# CH32V20xG8-R0.net
KiCad netlist of a schematic drawn in Altium Designer
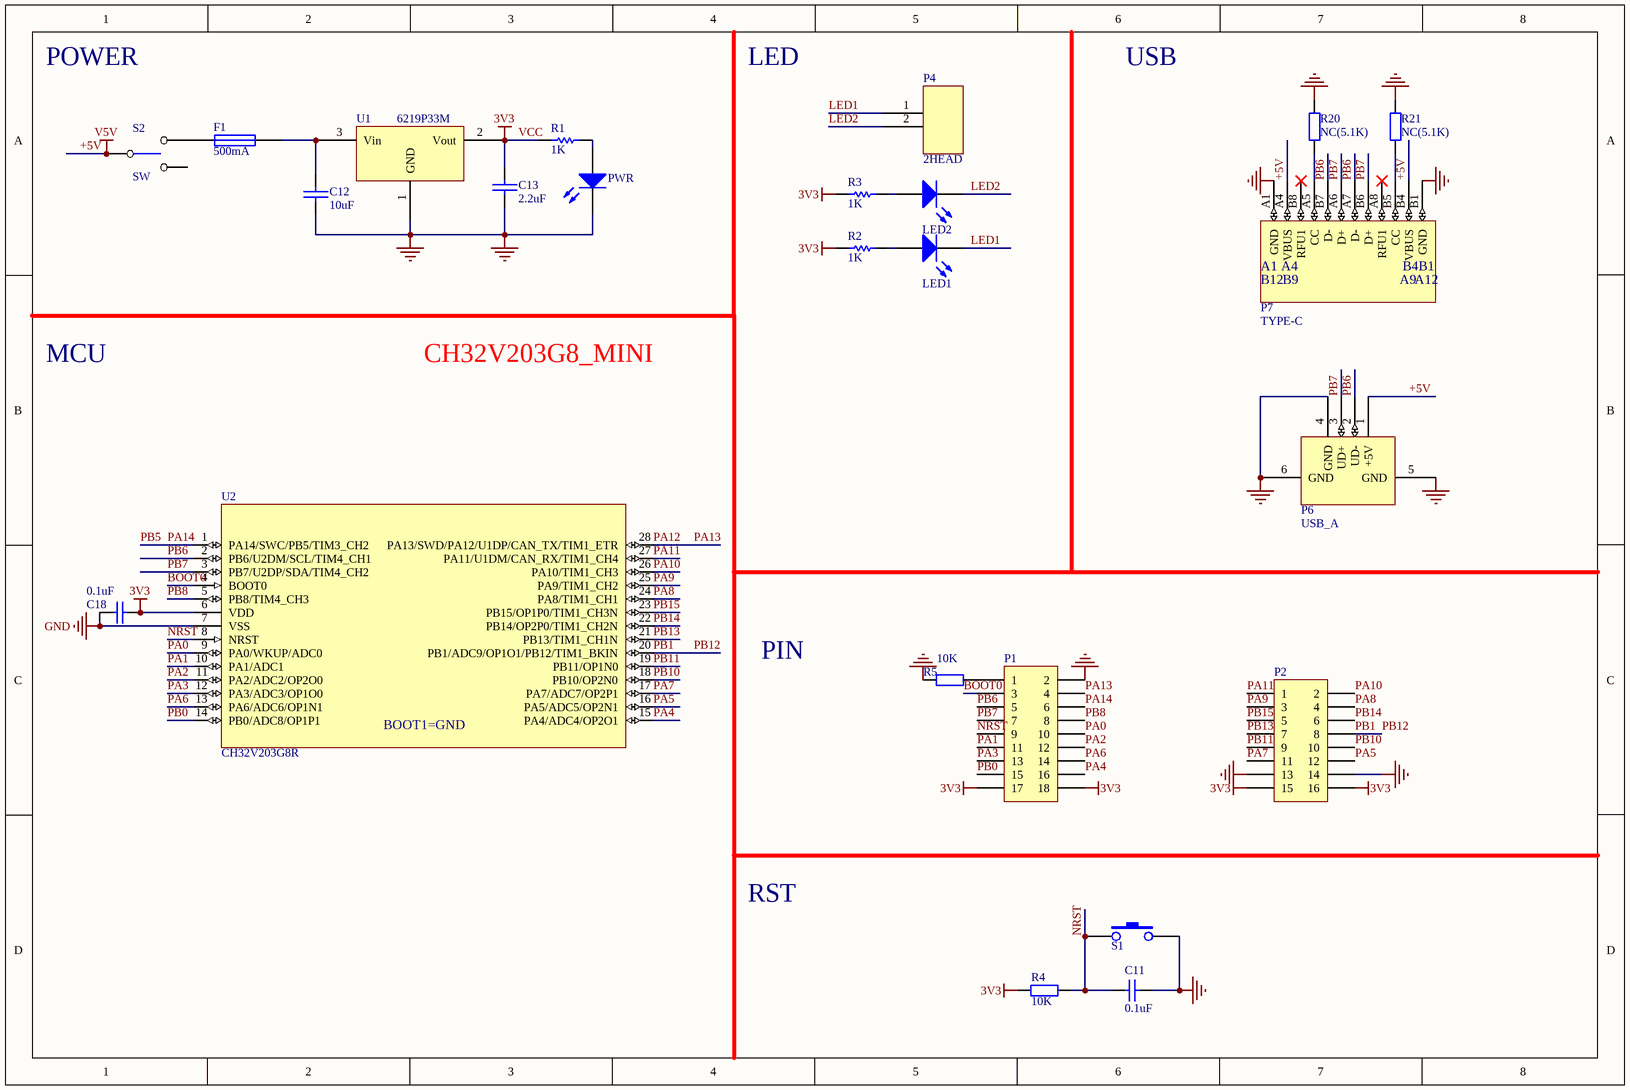
[diagram p0: CH32V20xG8-R0.SchDoc]

(export (version "E")
  (design (tool "Eeschema 10.0.6"))
  (components
    (comp (ref "C11")
      (value "0.1uF")
      (footprint "0603_C")
      (description "Capacitor")
      (fields (field (name "PUBLISHER") "Altium Limited"))
      (libsource (lib "*") (part "Cap"))
    )
    (comp (ref "C12")
      (value "10uF")
      (footprint "3216_C")
      (description "Capacitor")
      (libsource (lib "wch_sch_others") (part "CAP"))
    )
    (comp (ref "C13")
      (value "2.2uF")
      (footprint "0603_C")
      (description "Capacitor")
      (libsource (lib "wch_sch_others") (part "CAP"))
    )
    (comp (ref "C18")
      (value "0.1uF")
      (footprint "0603_C")
      (description "Capacitor")
      (fields (field (name "PUBLISHER") "Altium Limited"))
      (libsource (lib "*") (part "Cap"))
    )
    (comp (ref "F1")
      (value "500mA")
      (footprint "0603")
      (description "Fuse")
      (libsource (lib "*") (part "FUSE1"))
    )
    (comp (ref "LED1")
      (value "LED1   blue")
      (footprint "0603+")
      (description "Typical INFRARED GaAs LED")
      (fields (field (name "PUBLISHER") "Altium Limited"))
      (libsource (lib "*") (part "LED0"))
    )
    (comp (ref "LED2")
      (value "LED2  blue")
      (footprint "0603+")
      (description "Typical INFRARED GaAs LED")
      (fields (field (name "PUBLISHER") "Altium Limited"))
      (libsource (lib "*") (part "LED0"))
    )
    (comp (ref "P1")
      (value "Header 9X2")
      (footprint "IDC18-2.54mm")
      (description "Header, 9-Pin, Dual row")
      (fields (field (name "PUBLISHER") "Altium Limited"))
      (libsource (lib "Miscellaneous Connectors") (part "Header 9X2"))
    )
    (comp (ref "P2")
      (value "Header 8X2")
      (footprint "IDC16-2.54mm")
      (description "Header, 8-Pin, Dual row")
      (fields (field (name "PUBLISHER") "Altium Limited"))
      (libsource (lib "Miscellaneous Connectors") (part "Header 8X2"))
    )
    (comp (ref "P4") (value "2HEAD") (footprint "SIP2-2.54mm") (libsource (lib "*") (part "2HEAD")))
    (comp (ref "P6")
      (value "USB_A")
      (footprint "USBAF")
      (description "USB Port")
      (libsource (lib "*") (part "USB"))
    )
    (comp (ref "P7")
      (value "TYPE-C")
      (footprint "TYPE-C-Receptacle-2.0")
      (libsource (lib "*") (part "TYPE-C1"))
    )
    (comp (ref "PWR")
      (value "POWER  red")
      (footprint "0603+")
      (description "Typical INFRARED GaAs LED")
      (fields (field (name "PUBLISHER") "Altium Limited"))
      (libsource (lib "*") (part "LED0"))
    )
    (comp (ref "R1")
      (value "1K")
      (footprint "0603")
      (description "Semiconductor Resistor")
      (fields (field (name "PUBLISHER") "Altium Limited"))
      (libsource (lib "*") (part "Res Semi"))
    )
    (comp (ref "R2")
      (value "1K")
      (footprint "0603")
      (description "Semiconductor Resistor")
      (fields (field (name "PUBLISHER") "Altium Limited"))
      (libsource (lib "*") (part "Res Semi"))
    )
    (comp (ref "R3")
      (value "1K")
      (footprint "0603")
      (description "Semiconductor Resistor")
      (fields (field (name "PUBLISHER") "Altium Limited"))
      (libsource (lib "*") (part "Res Semi"))
    )
    (comp (ref "R4")
      (value "10K")
      (footprint "0603")
      (description "Resistor")
      (fields (field (name "PUBLISHER") "Altium Limited"))
      (libsource (lib "") (part "Res2_1"))
    )
    (comp (ref "R5")
      (value "10K")
      (footprint "0603")
      (description "Resistor")
      (fields (field (name "PUBLISHER") "Altium Limited"))
      (libsource (lib "*") (part "Res2"))
    )
    (comp (ref "R20")
      (value "NC(5.1K)")
      (footprint "0603")
      (description "Resistor")
      (libsource (lib "Miscellaneous Devices") (part "Res2"))
    )
    (comp (ref "R21")
      (value "NC(5.1K)")
      (footprint "0603")
      (description "Resistor")
      (libsource (lib "Miscellaneous Devices") (part "Res2"))
    )
    (comp (ref "S1") (value "NRST") (footprint "SMD_6.1x3.65x2.5mm-KEY") (libsource (lib "*") (part "KEY")))
    (comp (ref "S2") (value "SW") (footprint "KEY2") (libsource (lib "*") (part "SW")))
    (comp (ref "U1")
      (value "6219P33M")
      (footprint "SOT-23")
      (libsource (lib "wch_sch_others") (part "6219P33M"))
    )
    (comp (ref "U2")
      (value "CH32V203G8R")
      (footprint "QSOP28")
      (description "RISC-V LMD-MCU, 144MHz, for motor & wireless charging")
      (libsource (lib "CHXXX") (part "CH32V203G8R"))
    )
  )
  (nets
    (net (code "2") (name "/BOOT0") (class "Default")
      (node (ref "P1") (pin "3") (pinfunction "3_3") (pintype "passive"))
      (node (ref "U2") (pin "4") (pinfunction "BOOT0_4") (pintype "input"))
    )
    (net (code "3") (name "/LED1") (class "Default")
      (node (ref "LED1") (pin "2") (pinfunction "K_2") (pintype "passive"))
      (node (ref "P4") (pin "1") (pintype "passive"))
    )
    (net (code "4") (name "/LED2") (class "Default")
      (node (ref "LED2") (pin "2") (pinfunction "K_2") (pintype "passive"))
      (node (ref "P4") (pin "2") (pintype "passive"))
    )
    (net (code "5") (name "/NRST") (class "Default")
      (node (ref "C11") (pin "2") (pinfunction "2_2") (pintype "passive"))
      (node (ref "P1") (pin "9") (pinfunction "9_9") (pintype "passive"))
      (node (ref "R4") (pin "1") (pinfunction "1_1") (pintype "passive"))
      (node (ref "S1") (pin "1") (pinfunction "1_1") (pintype "passive"))
      (node (ref "U2") (pin "8") (pinfunction "NRST_8") (pintype "input"))
    )
    (net (code "6") (name "/PA0") (class "Default")
      (node (ref "P1") (pin "10") (pinfunction "10_10") (pintype "passive"))
      (node (ref "U2") (pin "9") (pinfunction "PA0/WKUP/ADC0_9") (pintype "bidirectional"))
    )
    (net (code "7") (name "/PA1") (class "Default")
      (node (ref "P1") (pin "11") (pinfunction "11_11") (pintype "passive"))
      (node (ref "U2") (pin "10") (pinfunction "PA1/ADC1_10") (pintype "bidirectional"))
    )
    (net (code "8") (name "/PA2") (class "Default")
      (node (ref "P1") (pin "12") (pinfunction "12_12") (pintype "passive"))
      (node (ref "U2") (pin "11") (pinfunction "PA2/ADC2/OP2O0_11") (pintype "bidirectional"))
    )
    (net (code "9") (name "/PA3") (class "Default")
      (node (ref "P1") (pin "13") (pinfunction "13_13") (pintype "passive"))
      (node (ref "U2") (pin "12") (pinfunction "PA3/ADC3/OP1O0_12") (pintype "bidirectional"))
    )
    (net (code "10") (name "/PA4") (class "Default")
      (node (ref "P1") (pin "16") (pinfunction "16_16") (pintype "passive"))
      (node (ref "U2") (pin "15") (pinfunction "PA4/ADC4/OP2O1_15") (pintype "bidirectional"))
    )
    (net (code "11") (name "/PA5") (class "Default")
      (node (ref "P2") (pin "12") (pinfunction "12_12") (pintype "passive"))
      (node (ref "U2") (pin "16") (pinfunction "PA5/ADC5/OP2N1_16") (pintype "bidirectional"))
    )
    (net (code "12") (name "/PA6") (class "Default")
      (node (ref "P1") (pin "14") (pinfunction "14_14") (pintype "passive"))
      (node (ref "U2") (pin "13") (pinfunction "PA6/ADC6/OP1N1_13") (pintype "bidirectional"))
    )
    (net (code "13") (name "/PA7") (class "Default")
      (node (ref "P2") (pin "11") (pinfunction "11_11") (pintype "passive"))
      (node (ref "U2") (pin "17") (pinfunction "PA7/ADC7/OP2P1_17") (pintype "bidirectional"))
    )
    (net (code "14") (name "/PA8") (class "Default")
      (node (ref "P2") (pin "4") (pinfunction "4_4") (pintype "passive"))
      (node (ref "U2") (pin "24") (pinfunction "PA8/TIM1_CH1_24") (pintype "bidirectional"))
    )
    (net (code "15") (name "/PA9") (class "Default")
      (node (ref "P2") (pin "3") (pinfunction "3_3") (pintype "passive"))
      (node (ref "U2") (pin "25") (pinfunction "PA9/TIM1_CH2_25") (pintype "bidirectional"))
    )
    (net (code "16") (name "/PA10") (class "Default")
      (node (ref "P2") (pin "2") (pinfunction "2_2") (pintype "passive"))
      (node (ref "U2") (pin "26") (pinfunction "PA10/TIM1_CH3_26") (pintype "bidirectional"))
    )
    (net (code "17") (name "/PA11") (class "Default")
      (node (ref "P2") (pin "1") (pinfunction "1_1") (pintype "passive"))
      (node (ref "U2") (pin "27") (pinfunction "PA11/U1DM/CAN_RX/TIM1_CH4_27") (pintype "bidirectional"))
    )
    (net (code "18") (name "/PA12") (class "Default")
      (node (ref "P1") (pin "4") (pinfunction "4_4") (pintype "passive"))
      (node (ref "U2") (pin "28") (pinfunction "PA13/SWD/PA12/U1DP/CAN_TX/TIM1_ETR_28") (pintype "bidirectional"))
    )
    (net (code "19") (name "/PA14") (class "Default")
      (node (ref "P1") (pin "6") (pinfunction "6_6") (pintype "passive"))
      (node (ref "U2") (pin "1") (pinfunction "PA14/SWC/PB5/TIM3_CH2_1") (pintype "bidirectional"))
    )
    (net (code "20") (name "/PB0") (class "Default")
      (node (ref "P1") (pin "15") (pinfunction "15_15") (pintype "passive"))
      (node (ref "U2") (pin "14") (pinfunction "PB0/ADC8/OP1P1_14") (pintype "bidirectional"))
    )
    (net (code "21") (name "/PB1") (class "Default")
      (node (ref "P2") (pin "8") (pinfunction "8_8") (pintype "passive"))
      (node (ref "U2") (pin "20") (pinfunction "PB1/ADC9/OP1O1/PB12/TIM1_BKIN_20") (pintype "bidirectional"))
    )
    (net (code "22") (name "/PB6") (class "Default")
      (node (ref "P1") (pin "5") (pinfunction "5_5") (pintype "passive"))
      (node (ref "P6") (pin "2") (pinfunction "UD-_2") (pintype "bidirectional"))
      (node (ref "P7") (pin "A7") (pinfunction "D-_A7") (pintype "bidirectional"))
      (node (ref "P7") (pin "B7") (pinfunction "D-_B7") (pintype "bidirectional"))
      (node (ref "U2") (pin "2") (pinfunction "PB6/U2DM/SCL/TIM4_CH1_2") (pintype "bidirectional"))
    )
    (net (code "23") (name "/PB7") (class "Default")
      (node (ref "P1") (pin "7") (pinfunction "7_7") (pintype "passive"))
      (node (ref "P6") (pin "3") (pinfunction "UD+_3") (pintype "bidirectional"))
      (node (ref "P7") (pin "A6") (pinfunction "D+_A6") (pintype "bidirectional"))
      (node (ref "P7") (pin "B6") (pinfunction "D+_B6") (pintype "bidirectional"))
      (node (ref "U2") (pin "3") (pinfunction "PB7/U2DP/SDA/TIM4_CH2_3") (pintype "bidirectional"))
    )
    (net (code "24") (name "/PB8") (class "Default")
      (node (ref "P1") (pin "8") (pinfunction "8_8") (pintype "passive"))
      (node (ref "U2") (pin "5") (pinfunction "PB8/TIM4_CH3_5") (pintype "bidirectional"))
    )
    (net (code "25") (name "/PB10") (class "Default")
      (node (ref "P2") (pin "10") (pinfunction "10_10") (pintype "passive"))
      (node (ref "U2") (pin "18") (pinfunction "PB10/OP2N0_18") (pintype "bidirectional"))
    )
    (net (code "26") (name "/PB11") (class "Default")
      (node (ref "P2") (pin "9") (pinfunction "9_9") (pintype "passive"))
      (node (ref "U2") (pin "19") (pinfunction "PB11/OP1N0_19") (pintype "bidirectional"))
    )
    (net (code "27") (name "/PB13") (class "Default")
      (node (ref "P2") (pin "7") (pinfunction "7_7") (pintype "passive"))
      (node (ref "U2") (pin "21") (pinfunction "PB13/TIM1_CH1N_21") (pintype "bidirectional"))
    )
    (net (code "28") (name "/PB14") (class "Default")
      (node (ref "P2") (pin "6") (pinfunction "6_6") (pintype "passive"))
      (node (ref "U2") (pin "22") (pinfunction "PB14/OP2P0/TIM1_CH2N_22") (pintype "bidirectional"))
    )
    (net (code "29") (name "/PB15") (class "Default")
      (node (ref "P2") (pin "5") (pinfunction "5_5") (pintype "passive"))
      (node (ref "U2") (pin "23") (pinfunction "PB15/OP1P0/TIM1_CH3N_23") (pintype "bidirectional"))
    )
    (net (code "30") (name "3V3") (class "Default")
      (node (ref "C13") (pin "2") (pinfunction "2_2") (pintype "passive"))
      (node (ref "C18") (pin "2") (pinfunction "2_2") (pintype "passive"))
      (node (ref "P1") (pin "17") (pinfunction "17_17") (pintype "passive"))
      (node (ref "P1") (pin "18") (pinfunction "18_18") (pintype "passive"))
      (node (ref "P2") (pin "15") (pinfunction "15_15") (pintype "passive"))
      (node (ref "P2") (pin "16") (pinfunction "16_16") (pintype "passive"))
      (node (ref "R1") (pin "2") (pinfunction "2_2") (pintype "passive"))
      (node (ref "R2") (pin "1") (pinfunction "1_1") (pintype "passive"))
      (node (ref "R3") (pin "1") (pinfunction "1_1") (pintype "passive"))
      (node (ref "R4") (pin "2") (pinfunction "2_2") (pintype "passive"))
      (node (ref "U1") (pin "2") (pinfunction "Vout_2") (pintype "passive"))
      (node (ref "U2") (pin "6") (pinfunction "VDD_6") (pintype "power_in"))
    )
    (net (code "31") (name "GND") (class "Default")
      (node (ref "C11") (pin "1") (pinfunction "1_1") (pintype "passive"))
      (node (ref "C12") (pin "2") (pinfunction "2_2") (pintype "passive"))
      (node (ref "C13") (pin "1") (pinfunction "1_1") (pintype "passive"))
      (node (ref "C18") (pin "1") (pinfunction "1_1") (pintype "passive"))
      (node (ref "P1") (pin "2") (pinfunction "2_2") (pintype "passive"))
      (node (ref "P2") (pin "13") (pinfunction "13_13") (pintype "passive"))
      (node (ref "P2") (pin "14") (pinfunction "14_14") (pintype "passive"))
      (node (ref "P6") (pin "4") (pinfunction "GND_4") (pintype "power_in"))
      (node (ref "P6") (pin "5") (pinfunction "GND_5") (pintype "power_in"))
      (node (ref "P6") (pin "6") (pinfunction "GND_6") (pintype "power_in"))
      (node (ref "P7") (pin "A1") (pinfunction "GND_A1") (pintype "bidirectional"))
      (node (ref "P7") (pin "B1") (pinfunction "GND_B1") (pintype "bidirectional"))
      (node (ref "PWR") (pin "2") (pinfunction "K_2") (pintype "passive"))
      (node (ref "R20") (pin "2") (pinfunction "2_2") (pintype "passive"))
      (node (ref "R21") (pin "2") (pinfunction "2_2") (pintype "passive"))
      (node (ref "R5") (pin "1") (pinfunction "1_1") (pintype "passive"))
      (node (ref "S1") (pin "2") (pinfunction "2_2") (pintype "passive"))
      (node (ref "U1") (pin "1") (pinfunction "GND_1") (pintype "passive"))
      (node (ref "U2") (pin "7") (pinfunction "VSS_7") (pintype "power_in"))
    )
    (net (code "32") (name "Net-(F1-Pad1)") (class "Default")
      (node (ref "F1") (pin "1") (pinfunction "1_1") (pintype "passive"))
      (node (ref "S2") (pin "3") (pinfunction "3_3") (pintype "passive"))
    )
    (net (code "33") (name "Net-(LED1-A)") (class "Default")
      (node (ref "LED1") (pin "1") (pinfunction "A_1") (pintype "passive"))
      (node (ref "R2") (pin "2") (pinfunction "2_2") (pintype "passive"))
    )
    (net (code "34") (name "Net-(LED2-A)") (class "Default")
      (node (ref "LED2") (pin "1") (pinfunction "A_1") (pintype "passive"))
      (node (ref "R3") (pin "2") (pinfunction "2_2") (pintype "passive"))
    )
    (net (code "35") (name "Net-(P1-Pad1)") (class "Default")
      (node (ref "P1") (pin "1") (pinfunction "1_1") (pintype "passive"))
      (node (ref "R5") (pin "2") (pinfunction "2_2") (pintype "passive"))
    )
    (net (code "36") (name "Net-(P7-CC-PadA5)") (class "Default")
      (node (ref "P7") (pin "A5") (pinfunction "CC_A5") (pintype "bidirectional"))
      (node (ref "R20") (pin "1") (pinfunction "1_1") (pintype "passive"))
    )
    (net (code "37") (name "Net-(P7-CC-PadB5)") (class "Default")
      (node (ref "P7") (pin "B5") (pinfunction "CC_B5") (pintype "bidirectional"))
      (node (ref "R21") (pin "1") (pinfunction "1_1") (pintype "passive"))
    )
    (net (code "38") (name "Net-(PWR-A)") (class "Default")
      (node (ref "PWR") (pin "1") (pinfunction "A_1") (pintype "passive"))
      (node (ref "R1") (pin "1") (pinfunction "1_1") (pintype "passive"))
    )
    (net (code "39") (name "Net-(U1-Vin)") (class "Default")
      (node (ref "C12") (pin "1") (pinfunction "1_1") (pintype "passive"))
      (node (ref "F1") (pin "2") (pinfunction "2_2") (pintype "passive"))
      (node (ref "U1") (pin "3") (pinfunction "Vin_3") (pintype "passive"))
    )
    (net (code "40") (name "V5V") (class "Default")
      (node (ref "P6") (pin "1") (pinfunction "+5V_1") (pintype "power_in"))
      (node (ref "P7") (pin "A4") (pinfunction "VBUS_A4") (pintype "bidirectional"))
      (node (ref "P7") (pin "B4") (pinfunction "VBUS_B4") (pintype "bidirectional"))
      (node (ref "S2") (pin "1") (pinfunction "1_1") (pintype "passive"))
    )
    (net (code "41") (name "unconnected-(P7-RFU1-PadA8)") (class "Default")
      (node (ref "P7") (pin "A8") (pinfunction "RFU1_A8") (pintype "bidirectional+no_connect"))
    )
    (net (code "42") (name "unconnected-(P7-RFU1-PadB8)") (class "Default")
      (node (ref "P7") (pin "B8") (pinfunction "RFU1_B8") (pintype "bidirectional+no_connect"))
    )
    (net (code "43") (name "unconnected-(S2-Pad2)") (class "Default")
      (node (ref "S2") (pin "2") (pinfunction "2_2") (pintype "passive"))
    )
  )
)
